# Level_Shifter.net
KiCad netlist of a schematic drawn in Altium Designer
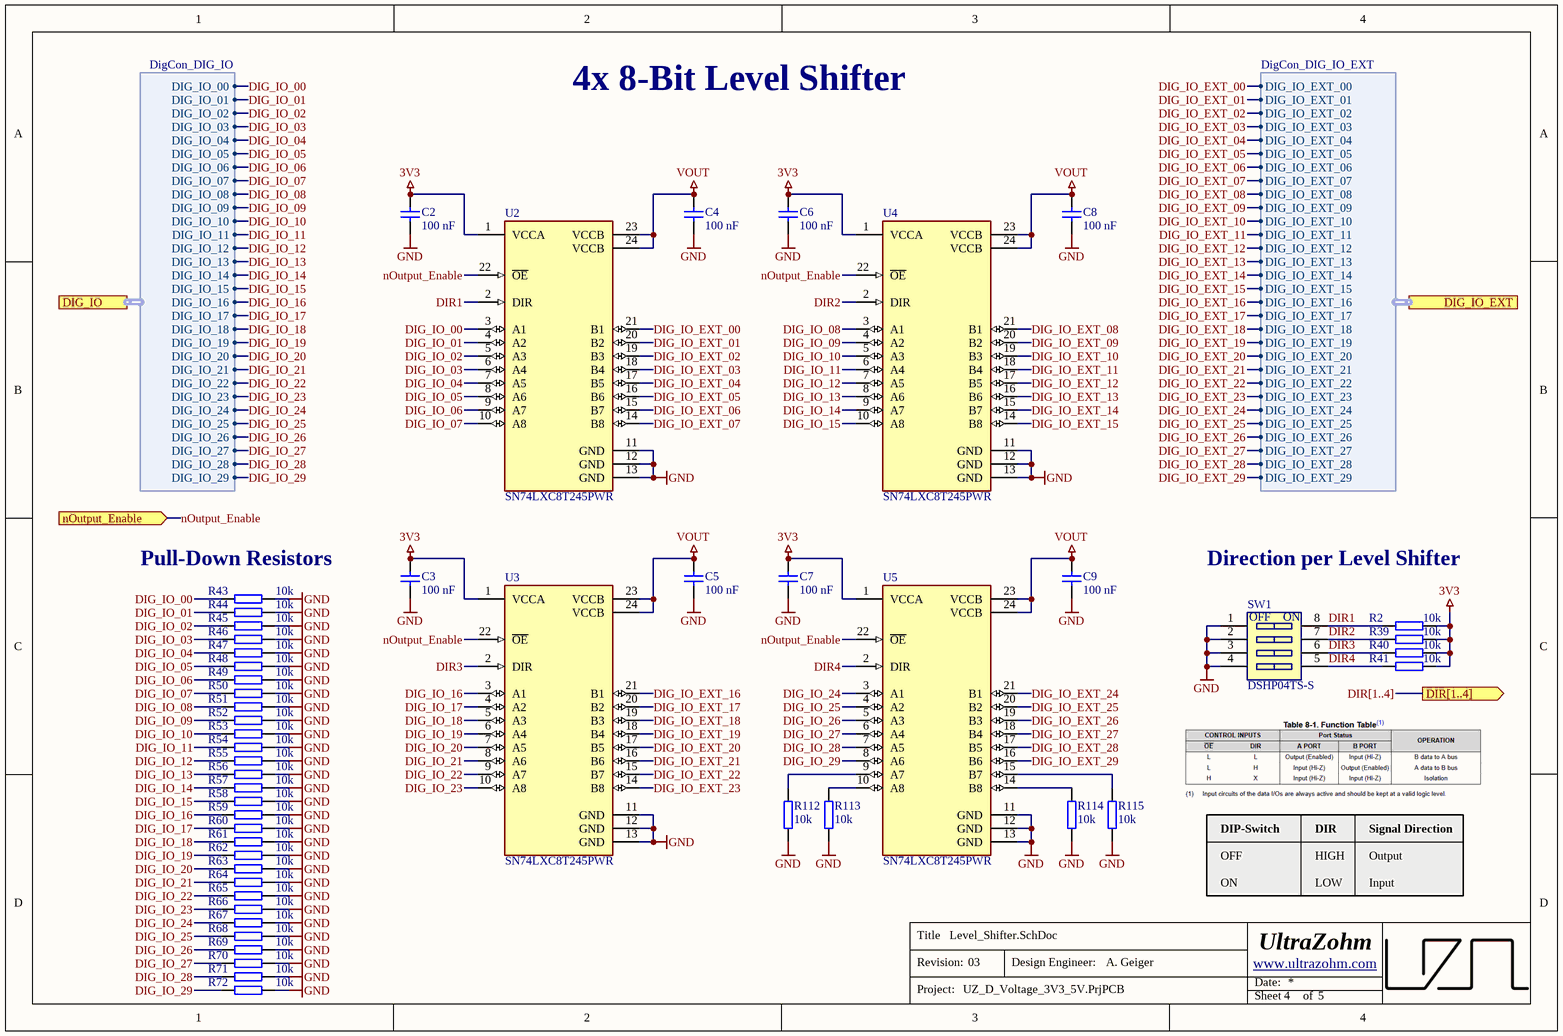
[diagram p0: Level_Shifter.SchDoc]

(export (version "E")
  (design (tool "Eeschema 10.0.6"))
  (components
    (comp (ref "C2")
      (value "100 nF")
      (footprint "C_0603_TE")
      (description "Generic capacitor")
      (fields
        (field (name "MANUFACTURER PART NUMBER") "UZgen_C_0603_100nF_50V_X7R")
        (field (name "MANUFACTURER") "UZgen")
        (field (name "CREATED FROM") "AGeiger")
      )
      (libsource (lib "user") (part "CAP-NP"))
    )
    (comp (ref "C3")
      (value "100 nF")
      (footprint "C_0603_TE")
      (description "Generic capacitor")
      (fields
        (field (name "MANUFACTURER PART NUMBER") "UZgen_C_0603_100nF_50V_X7R")
        (field (name "MANUFACTURER") "UZgen")
        (field (name "CREATED FROM") "AGeiger")
      )
      (libsource (lib "user") (part "CAP-NP"))
    )
    (comp (ref "C4")
      (value "100 nF")
      (footprint "C_0603_TE")
      (description "Generic capacitor")
      (fields
        (field (name "MANUFACTURER PART NUMBER") "UZgen_C_0603_100nF_50V_X7R")
        (field (name "MANUFACTURER") "UZgen")
        (field (name "CREATED FROM") "AGeiger")
      )
      (libsource (lib "user") (part "CAP-NP"))
    )
    (comp (ref "C5")
      (value "100 nF")
      (footprint "C_0603_TE")
      (description "Generic capacitor")
      (fields
        (field (name "MANUFACTURER PART NUMBER") "UZgen_C_0603_100nF_50V_X7R")
        (field (name "MANUFACTURER") "UZgen")
        (field (name "CREATED FROM") "AGeiger")
      )
      (libsource (lib "user") (part "CAP-NP"))
    )
    (comp (ref "C6")
      (value "100 nF")
      (footprint "C_0603_TE")
      (description "Generic capacitor")
      (fields
        (field (name "MANUFACTURER PART NUMBER") "UZgen_C_0603_100nF_50V_X7R")
        (field (name "MANUFACTURER") "UZgen")
        (field (name "CREATED FROM") "AGeiger")
      )
      (libsource (lib "user") (part "CAP-NP"))
    )
    (comp (ref "C7")
      (value "100 nF")
      (footprint "C_0603_TE")
      (description "Generic capacitor")
      (fields
        (field (name "MANUFACTURER PART NUMBER") "UZgen_C_0603_100nF_50V_X7R")
        (field (name "MANUFACTURER") "UZgen")
        (field (name "CREATED FROM") "AGeiger")
      )
      (libsource (lib "user") (part "CAP-NP"))
    )
    (comp (ref "C8")
      (value "100 nF")
      (footprint "C_0603_TE")
      (description "Generic capacitor")
      (fields
        (field (name "MANUFACTURER PART NUMBER") "UZgen_C_0603_100nF_50V_X7R")
        (field (name "MANUFACTURER") "UZgen")
        (field (name "CREATED FROM") "AGeiger")
      )
      (libsource (lib "user") (part "CAP-NP"))
    )
    (comp (ref "C9")
      (value "100 nF")
      (footprint "C_0603_TE")
      (description "Generic capacitor")
      (fields
        (field (name "MANUFACTURER PART NUMBER") "UZgen_C_0603_100nF_50V_X7R")
        (field (name "MANUFACTURER") "UZgen")
        (field (name "CREATED FROM") "AGeiger")
      )
      (libsource (lib "user") (part "CAP-NP"))
    )
    (comp (ref "R2")
      (value "10k")
      (footprint "R_0603_TE")
      (description "Generic resistor")
      (fields
        (field (name "MANUFACTURER PART NUMBER") "UZgen_R_0603_10k")
        (field (name "MANUFACTURER") "UZgen")
        (field (name "CREATED FROM") "AGeiger")
      )
      (libsource (lib "user") (part "RES"))
    )
    (comp (ref "R39")
      (value "10k")
      (footprint "R_0603_TE")
      (description "Generic resistor")
      (fields
        (field (name "MANUFACTURER PART NUMBER") "UZgen_R_0603_10k")
        (field (name "MANUFACTURER") "UZgen")
        (field (name "CREATED FROM") "AGeiger")
      )
      (libsource (lib "user") (part "RES"))
    )
    (comp (ref "R40")
      (value "10k")
      (footprint "R_0603_TE")
      (description "Generic resistor")
      (fields
        (field (name "MANUFACTURER PART NUMBER") "UZgen_R_0603_10k")
        (field (name "MANUFACTURER") "UZgen")
        (field (name "CREATED FROM") "AGeiger")
      )
      (libsource (lib "user") (part "RES"))
    )
    (comp (ref "R41")
      (value "10k")
      (footprint "R_0603_TE")
      (description "Generic resistor")
      (fields
        (field (name "MANUFACTURER PART NUMBER") "UZgen_R_0603_10k")
        (field (name "MANUFACTURER") "UZgen")
        (field (name "CREATED FROM") "AGeiger")
      )
      (libsource (lib "user") (part "RES"))
    )
    (comp (ref "R43")
      (value "10k")
      (footprint "R_0603_TE")
      (description "Generic resistor")
      (fields
        (field (name "MANUFACTURER PART NUMBER") "UZgen_R_0603_10k")
        (field (name "MANUFACTURER") "UZgen")
        (field (name "CREATED FROM") "AGeiger")
      )
      (libsource (lib "user") (part "RES"))
    )
    (comp (ref "R44")
      (value "10k")
      (footprint "R_0603_TE")
      (description "Generic resistor")
      (fields
        (field (name "MANUFACTURER PART NUMBER") "UZgen_R_0603_10k")
        (field (name "MANUFACTURER") "UZgen")
        (field (name "CREATED FROM") "AGeiger")
      )
      (libsource (lib "user") (part "RES"))
    )
    (comp (ref "R45")
      (value "10k")
      (footprint "R_0603_TE")
      (description "Generic resistor")
      (fields
        (field (name "MANUFACTURER PART NUMBER") "UZgen_R_0603_10k")
        (field (name "MANUFACTURER") "UZgen")
        (field (name "CREATED FROM") "AGeiger")
      )
      (libsource (lib "user") (part "RES"))
    )
    (comp (ref "R46")
      (value "10k")
      (footprint "R_0603_TE")
      (description "Generic resistor")
      (fields
        (field (name "MANUFACTURER PART NUMBER") "UZgen_R_0603_10k")
        (field (name "MANUFACTURER") "UZgen")
        (field (name "CREATED FROM") "AGeiger")
      )
      (libsource (lib "user") (part "RES"))
    )
    (comp (ref "R47")
      (value "10k")
      (footprint "R_0603_TE")
      (description "Generic resistor")
      (fields
        (field (name "MANUFACTURER PART NUMBER") "UZgen_R_0603_10k")
        (field (name "MANUFACTURER") "UZgen")
        (field (name "CREATED FROM") "AGeiger")
      )
      (libsource (lib "user") (part "RES"))
    )
    (comp (ref "R48")
      (value "10k")
      (footprint "R_0603_TE")
      (description "Generic resistor")
      (fields
        (field (name "MANUFACTURER PART NUMBER") "UZgen_R_0603_10k")
        (field (name "MANUFACTURER") "UZgen")
        (field (name "CREATED FROM") "AGeiger")
      )
      (libsource (lib "user") (part "RES"))
    )
    (comp (ref "R49")
      (value "10k")
      (footprint "R_0603_TE")
      (description "Generic resistor")
      (fields
        (field (name "MANUFACTURER PART NUMBER") "UZgen_R_0603_10k")
        (field (name "MANUFACTURER") "UZgen")
        (field (name "CREATED FROM") "AGeiger")
      )
      (libsource (lib "user") (part "RES"))
    )
    (comp (ref "R50")
      (value "10k")
      (footprint "R_0603_TE")
      (description "Generic resistor")
      (fields
        (field (name "MANUFACTURER PART NUMBER") "UZgen_R_0603_10k")
        (field (name "MANUFACTURER") "UZgen")
        (field (name "CREATED FROM") "AGeiger")
      )
      (libsource (lib "user") (part "RES"))
    )
    (comp (ref "R51")
      (value "10k")
      (footprint "R_0603_TE")
      (description "Generic resistor")
      (fields
        (field (name "MANUFACTURER PART NUMBER") "UZgen_R_0603_10k")
        (field (name "MANUFACTURER") "UZgen")
        (field (name "CREATED FROM") "AGeiger")
      )
      (libsource (lib "user") (part "RES"))
    )
    (comp (ref "R52")
      (value "10k")
      (footprint "R_0603_TE")
      (description "Generic resistor")
      (fields
        (field (name "MANUFACTURER PART NUMBER") "UZgen_R_0603_10k")
        (field (name "MANUFACTURER") "UZgen")
        (field (name "CREATED FROM") "AGeiger")
      )
      (libsource (lib "user") (part "RES"))
    )
    (comp (ref "R53")
      (value "10k")
      (footprint "R_0603_TE")
      (description "Generic resistor")
      (fields
        (field (name "MANUFACTURER PART NUMBER") "UZgen_R_0603_10k")
        (field (name "MANUFACTURER") "UZgen")
        (field (name "CREATED FROM") "AGeiger")
      )
      (libsource (lib "user") (part "RES"))
    )
    (comp (ref "R54")
      (value "10k")
      (footprint "R_0603_TE")
      (description "Generic resistor")
      (fields
        (field (name "MANUFACTURER PART NUMBER") "UZgen_R_0603_10k")
        (field (name "MANUFACTURER") "UZgen")
        (field (name "CREATED FROM") "AGeiger")
      )
      (libsource (lib "user") (part "RES"))
    )
    (comp (ref "R55")
      (value "10k")
      (footprint "R_0603_TE")
      (description "Generic resistor")
      (fields
        (field (name "MANUFACTURER PART NUMBER") "UZgen_R_0603_10k")
        (field (name "MANUFACTURER") "UZgen")
        (field (name "CREATED FROM") "AGeiger")
      )
      (libsource (lib "user") (part "RES"))
    )
    (comp (ref "R56")
      (value "10k")
      (footprint "R_0603_TE")
      (description "Generic resistor")
      (fields
        (field (name "MANUFACTURER PART NUMBER") "UZgen_R_0603_10k")
        (field (name "MANUFACTURER") "UZgen")
        (field (name "CREATED FROM") "AGeiger")
      )
      (libsource (lib "user") (part "RES"))
    )
    (comp (ref "R57")
      (value "10k")
      (footprint "R_0603_TE")
      (description "Generic resistor")
      (fields
        (field (name "MANUFACTURER PART NUMBER") "UZgen_R_0603_10k")
        (field (name "MANUFACTURER") "UZgen")
        (field (name "CREATED FROM") "AGeiger")
      )
      (libsource (lib "user") (part "RES"))
    )
    (comp (ref "R58")
      (value "10k")
      (footprint "R_0603_TE")
      (description "Generic resistor")
      (fields
        (field (name "MANUFACTURER PART NUMBER") "UZgen_R_0603_10k")
        (field (name "MANUFACTURER") "UZgen")
        (field (name "CREATED FROM") "AGeiger")
      )
      (libsource (lib "user") (part "RES"))
    )
    (comp (ref "R59")
      (value "10k")
      (footprint "R_0603_TE")
      (description "Generic resistor")
      (fields
        (field (name "MANUFACTURER PART NUMBER") "UZgen_R_0603_10k")
        (field (name "MANUFACTURER") "UZgen")
        (field (name "CREATED FROM") "AGeiger")
      )
      (libsource (lib "user") (part "RES"))
    )
    (comp (ref "R60")
      (value "10k")
      (footprint "R_0603_TE")
      (description "Generic resistor")
      (fields
        (field (name "MANUFACTURER PART NUMBER") "UZgen_R_0603_10k")
        (field (name "MANUFACTURER") "UZgen")
        (field (name "CREATED FROM") "AGeiger")
      )
      (libsource (lib "user") (part "RES"))
    )
    (comp (ref "R61")
      (value "10k")
      (footprint "R_0603_TE")
      (description "Generic resistor")
      (fields
        (field (name "MANUFACTURER PART NUMBER") "UZgen_R_0603_10k")
        (field (name "MANUFACTURER") "UZgen")
        (field (name "CREATED FROM") "AGeiger")
      )
      (libsource (lib "user") (part "RES"))
    )
    (comp (ref "R62")
      (value "10k")
      (footprint "R_0603_TE")
      (description "Generic resistor")
      (fields
        (field (name "MANUFACTURER PART NUMBER") "UZgen_R_0603_10k")
        (field (name "MANUFACTURER") "UZgen")
        (field (name "CREATED FROM") "AGeiger")
      )
      (libsource (lib "user") (part "RES"))
    )
    (comp (ref "R63")
      (value "10k")
      (footprint "R_0603_TE")
      (description "Generic resistor")
      (fields
        (field (name "MANUFACTURER PART NUMBER") "UZgen_R_0603_10k")
        (field (name "MANUFACTURER") "UZgen")
        (field (name "CREATED FROM") "AGeiger")
      )
      (libsource (lib "user") (part "RES"))
    )
    (comp (ref "R64")
      (value "10k")
      (footprint "R_0603_TE")
      (description "Generic resistor")
      (fields
        (field (name "MANUFACTURER PART NUMBER") "UZgen_R_0603_10k")
        (field (name "MANUFACTURER") "UZgen")
        (field (name "CREATED FROM") "AGeiger")
      )
      (libsource (lib "user") (part "RES"))
    )
    (comp (ref "R65")
      (value "10k")
      (footprint "R_0603_TE")
      (description "Generic resistor")
      (fields
        (field (name "MANUFACTURER PART NUMBER") "UZgen_R_0603_10k")
        (field (name "MANUFACTURER") "UZgen")
        (field (name "CREATED FROM") "AGeiger")
      )
      (libsource (lib "user") (part "RES"))
    )
    (comp (ref "R66")
      (value "10k")
      (footprint "R_0603_TE")
      (description "Generic resistor")
      (fields
        (field (name "MANUFACTURER PART NUMBER") "UZgen_R_0603_10k")
        (field (name "MANUFACTURER") "UZgen")
        (field (name "CREATED FROM") "AGeiger")
      )
      (libsource (lib "user") (part "RES"))
    )
    (comp (ref "R67")
      (value "10k")
      (footprint "R_0603_TE")
      (description "Generic resistor")
      (fields
        (field (name "MANUFACTURER PART NUMBER") "UZgen_R_0603_10k")
        (field (name "MANUFACTURER") "UZgen")
        (field (name "CREATED FROM") "AGeiger")
      )
      (libsource (lib "user") (part "RES"))
    )
    (comp (ref "R68")
      (value "10k")
      (footprint "R_0603_TE")
      (description "Generic resistor")
      (fields
        (field (name "MANUFACTURER PART NUMBER") "UZgen_R_0603_10k")
        (field (name "MANUFACTURER") "UZgen")
        (field (name "CREATED FROM") "AGeiger")
      )
      (libsource (lib "user") (part "RES"))
    )
    (comp (ref "R69")
      (value "10k")
      (footprint "R_0603_TE")
      (description "Generic resistor")
      (fields
        (field (name "MANUFACTURER PART NUMBER") "UZgen_R_0603_10k")
        (field (name "MANUFACTURER") "UZgen")
        (field (name "CREATED FROM") "AGeiger")
      )
      (libsource (lib "user") (part "RES"))
    )
    (comp (ref "R70")
      (value "10k")
      (footprint "R_0603_TE")
      (description "Generic resistor")
      (fields
        (field (name "MANUFACTURER PART NUMBER") "UZgen_R_0603_10k")
        (field (name "MANUFACTURER") "UZgen")
        (field (name "CREATED FROM") "AGeiger")
      )
      (libsource (lib "user") (part "RES"))
    )
    (comp (ref "R71")
      (value "10k")
      (footprint "R_0603_TE")
      (description "Generic resistor")
      (fields
        (field (name "MANUFACTURER PART NUMBER") "UZgen_R_0603_10k")
        (field (name "MANUFACTURER") "UZgen")
        (field (name "CREATED FROM") "AGeiger")
      )
      (libsource (lib "user") (part "RES"))
    )
    (comp (ref "R72")
      (value "10k")
      (footprint "R_0603_TE")
      (description "Generic resistor")
      (fields
        (field (name "MANUFACTURER PART NUMBER") "UZgen_R_0603_10k")
        (field (name "MANUFACTURER") "UZgen")
        (field (name "CREATED FROM") "AGeiger")
      )
      (libsource (lib "user") (part "RES"))
    )
    (comp (ref "R112")
      (value "10k")
      (footprint "R_0603_TE")
      (description "Generic resistor")
      (fields
        (field (name "MANUFACTURER PART NUMBER") "UZgen_R_0603_10k")
        (field (name "MANUFACTURER") "UZgen")
        (field (name "CREATED FROM") "AGeiger")
      )
      (libsource (lib "user") (part "RES"))
    )
    (comp (ref "R113")
      (value "10k")
      (footprint "R_0603_TE")
      (description "Generic resistor")
      (fields
        (field (name "MANUFACTURER PART NUMBER") "UZgen_R_0603_10k")
        (field (name "MANUFACTURER") "UZgen")
        (field (name "CREATED FROM") "AGeiger")
      )
      (libsource (lib "user") (part "RES"))
    )
    (comp (ref "R114")
      (value "10k")
      (footprint "R_0603_TE")
      (description "Generic resistor")
      (fields
        (field (name "MANUFACTURER PART NUMBER") "UZgen_R_0603_10k")
        (field (name "MANUFACTURER") "UZgen")
        (field (name "CREATED FROM") "AGeiger")
      )
      (libsource (lib "user") (part "RES"))
    )
    (comp (ref "R115")
      (value "10k")
      (footprint "R_0603_TE")
      (description "Generic resistor")
      (fields
        (field (name "MANUFACTURER PART NUMBER") "UZgen_R_0603_10k")
        (field (name "MANUFACTURER") "UZgen")
        (field (name "CREATED FROM") "AGeiger")
      )
      (libsource (lib "user") (part "RES"))
    )
    (comp (ref "SW1")
      (value "DSHP04TS-S")
      (footprint "416131160804")
      (description "04p, 1.27mm Pitch, Horizontal, HP Type, SMT, flat Actuator, black, with Tape, T&R")
      (fields
        (field (name "MANUFACTURER") "XKB Connectivity")
        (field (name "LCSC PART NUMBER") "C319050")
        (field (name "CREATED FROM") "T. Wendt")
      )
      (libsource (lib "user") (part "DIP-SW-4p"))
    )
    (comp (ref "U2")
      (value "SN74LXC8T245PWR")
      (footprint "TSSOP-24")
      (description "8-bit Dual-Supply Bus Transceiver with Configurable Level Shifting and 3-State Outputs")
      (fields
        (field (name "MANUFACTURER") "Texas Instruments")
        (field (name "LCSC PART NUMBER") "C4363995")
        (field (name "CREATED FROM") "AGeiger")
      )
      (libsource (lib "user") (part "SN74LXC8T245"))
    )
    (comp (ref "U3")
      (value "SN74LXC8T245PWR")
      (footprint "TSSOP-24")
      (description "8-bit Dual-Supply Bus Transceiver with Configurable Level Shifting and 3-State Outputs")
      (fields
        (field (name "MANUFACTURER") "Texas Instruments")
        (field (name "LCSC PART NUMBER") "C4363995")
        (field (name "CREATED FROM") "AGeiger")
      )
      (libsource (lib "user") (part "SN74LXC8T245"))
    )
    (comp (ref "U4")
      (value "SN74LXC8T245PWR")
      (footprint "TSSOP-24")
      (description "8-bit Dual-Supply Bus Transceiver with Configurable Level Shifting and 3-State Outputs")
      (fields
        (field (name "MANUFACTURER") "Texas Instruments")
        (field (name "LCSC PART NUMBER") "C4363995")
        (field (name "CREATED FROM") "AGeiger")
      )
      (libsource (lib "user") (part "SN74LXC8T245"))
    )
    (comp (ref "U5")
      (value "SN74LXC8T245PWR")
      (footprint "TSSOP-24")
      (description "8-bit Dual-Supply Bus Transceiver with Configurable Level Shifting and 3-State Outputs")
      (fields
        (field (name "MANUFACTURER") "Texas Instruments")
        (field (name "LCSC PART NUMBER") "C4363995")
        (field (name "CREATED FROM") "AGeiger")
      )
      (libsource (lib "user") (part "SN74LXC8T245"))
    )
  )
  (nets
    (net (code "3") (name "/DIG_IO_00") (class "Default")
      (node (ref "R43") (pin "1") (pinfunction "1_1") (pintype "passive"))
      (node (ref "U2") (pin "3") (pinfunction "A1_3") (pintype "bidirectional"))
    )
    (net (code "4") (name "/DIG_IO_01") (class "Default")
      (node (ref "R44") (pin "1") (pinfunction "1_1") (pintype "passive"))
      (node (ref "U2") (pin "4") (pinfunction "A2_4") (pintype "bidirectional"))
    )
    (net (code "5") (name "/DIG_IO_02") (class "Default")
      (node (ref "R45") (pin "1") (pinfunction "1_1") (pintype "passive"))
      (node (ref "U2") (pin "5") (pinfunction "A3_5") (pintype "bidirectional"))
    )
    (net (code "6") (name "/DIG_IO_03") (class "Default")
      (node (ref "R46") (pin "1") (pinfunction "1_1") (pintype "passive"))
      (node (ref "U2") (pin "6") (pinfunction "A4_6") (pintype "bidirectional"))
    )
    (net (code "7") (name "/DIG_IO_04") (class "Default")
      (node (ref "R47") (pin "1") (pinfunction "1_1") (pintype "passive"))
      (node (ref "U2") (pin "7") (pinfunction "A5_7") (pintype "bidirectional"))
    )
    (net (code "8") (name "/DIG_IO_05") (class "Default")
      (node (ref "R48") (pin "1") (pinfunction "1_1") (pintype "passive"))
      (node (ref "U2") (pin "8") (pinfunction "A6_8") (pintype "bidirectional"))
    )
    (net (code "9") (name "/DIG_IO_06") (class "Default")
      (node (ref "R49") (pin "1") (pinfunction "1_1") (pintype "passive"))
      (node (ref "U2") (pin "9") (pinfunction "A7_9") (pintype "bidirectional"))
    )
    (net (code "10") (name "/DIG_IO_07") (class "Default")
      (node (ref "R50") (pin "1") (pinfunction "1_1") (pintype "passive"))
      (node (ref "U2") (pin "10") (pinfunction "A8_10") (pintype "bidirectional"))
    )
    (net (code "11") (name "/DIG_IO_08") (class "Default")
      (node (ref "R51") (pin "1") (pinfunction "1_1") (pintype "passive"))
      (node (ref "U4") (pin "3") (pinfunction "A1_3") (pintype "bidirectional"))
    )
    (net (code "12") (name "/DIG_IO_09") (class "Default")
      (node (ref "R52") (pin "1") (pinfunction "1_1") (pintype "passive"))
      (node (ref "U4") (pin "4") (pinfunction "A2_4") (pintype "bidirectional"))
    )
    (net (code "13") (name "/DIG_IO_10") (class "Default")
      (node (ref "R53") (pin "1") (pinfunction "1_1") (pintype "passive"))
      (node (ref "U4") (pin "5") (pinfunction "A3_5") (pintype "bidirectional"))
    )
    (net (code "14") (name "/DIG_IO_11") (class "Default")
      (node (ref "R54") (pin "1") (pinfunction "1_1") (pintype "passive"))
      (node (ref "U4") (pin "6") (pinfunction "A4_6") (pintype "bidirectional"))
    )
    (net (code "15") (name "/DIG_IO_12") (class "Default")
      (node (ref "R55") (pin "1") (pinfunction "1_1") (pintype "passive"))
      (node (ref "U4") (pin "7") (pinfunction "A5_7") (pintype "bidirectional"))
    )
    (net (code "16") (name "/DIG_IO_13") (class "Default")
      (node (ref "R56") (pin "1") (pinfunction "1_1") (pintype "passive"))
      (node (ref "U4") (pin "8") (pinfunction "A6_8") (pintype "bidirectional"))
    )
    (net (code "17") (name "/DIG_IO_14") (class "Default")
      (node (ref "R57") (pin "1") (pinfunction "1_1") (pintype "passive"))
      (node (ref "U4") (pin "9") (pinfunction "A7_9") (pintype "bidirectional"))
    )
    (net (code "18") (name "/DIG_IO_15") (class "Default")
      (node (ref "R58") (pin "1") (pinfunction "1_1") (pintype "passive"))
      (node (ref "U4") (pin "10") (pinfunction "A8_10") (pintype "bidirectional"))
    )
    (net (code "19") (name "/DIG_IO_16") (class "Default")
      (node (ref "R59") (pin "1") (pinfunction "1_1") (pintype "passive"))
      (node (ref "U3") (pin "3") (pinfunction "A1_3") (pintype "bidirectional"))
    )
    (net (code "20") (name "/DIG_IO_17") (class "Default")
      (node (ref "R60") (pin "1") (pinfunction "1_1") (pintype "passive"))
      (node (ref "U3") (pin "4") (pinfunction "A2_4") (pintype "bidirectional"))
    )
    (net (code "21") (name "/DIG_IO_18") (class "Default")
      (node (ref "R61") (pin "1") (pinfunction "1_1") (pintype "passive"))
      (node (ref "U3") (pin "5") (pinfunction "A3_5") (pintype "bidirectional"))
    )
    (net (code "22") (name "/DIG_IO_19") (class "Default")
      (node (ref "R62") (pin "1") (pinfunction "1_1") (pintype "passive"))
      (node (ref "U3") (pin "6") (pinfunction "A4_6") (pintype "bidirectional"))
    )
    (net (code "23") (name "/DIG_IO_20") (class "Default")
      (node (ref "R63") (pin "1") (pinfunction "1_1") (pintype "passive"))
      (node (ref "U3") (pin "7") (pinfunction "A5_7") (pintype "bidirectional"))
    )
    (net (code "24") (name "/DIG_IO_21") (class "Default")
      (node (ref "R64") (pin "1") (pinfunction "1_1") (pintype "passive"))
      (node (ref "U3") (pin "8") (pinfunction "A6_8") (pintype "bidirectional"))
    )
    (net (code "25") (name "/DIG_IO_22") (class "Default")
      (node (ref "R65") (pin "1") (pinfunction "1_1") (pintype "passive"))
      (node (ref "U3") (pin "9") (pinfunction "A7_9") (pintype "bidirectional"))
    )
    (net (code "26") (name "/DIG_IO_23") (class "Default")
      (node (ref "R66") (pin "1") (pinfunction "1_1") (pintype "passive"))
      (node (ref "U3") (pin "10") (pinfunction "A8_10") (pintype "bidirectional"))
    )
    (net (code "27") (name "/DIG_IO_24") (class "Default")
      (node (ref "R67") (pin "1") (pinfunction "1_1") (pintype "passive"))
      (node (ref "U5") (pin "3") (pinfunction "A1_3") (pintype "bidirectional"))
    )
    (net (code "28") (name "/DIG_IO_25") (class "Default")
      (node (ref "R68") (pin "1") (pinfunction "1_1") (pintype "passive"))
      (node (ref "U5") (pin "4") (pinfunction "A2_4") (pintype "bidirectional"))
    )
    (net (code "29") (name "/DIG_IO_26") (class "Default")
      (node (ref "R69") (pin "1") (pinfunction "1_1") (pintype "passive"))
      (node (ref "U5") (pin "5") (pinfunction "A3_5") (pintype "bidirectional"))
    )
    (net (code "30") (name "/DIG_IO_27") (class "Default")
      (node (ref "R70") (pin "1") (pinfunction "1_1") (pintype "passive"))
      (node (ref "U5") (pin "6") (pinfunction "A4_6") (pintype "bidirectional"))
    )
    (net (code "31") (name "/DIG_IO_28") (class "Default")
      (node (ref "R71") (pin "1") (pinfunction "1_1") (pintype "passive"))
      (node (ref "U5") (pin "7") (pinfunction "A5_7") (pintype "bidirectional"))
    )
    (net (code "32") (name "/DIG_IO_29") (class "Default")
      (node (ref "R72") (pin "1") (pinfunction "1_1") (pintype "passive"))
      (node (ref "U5") (pin "8") (pinfunction "A6_8") (pintype "bidirectional"))
    )
    (net (code "33") (name "/DIG_IO_EXT_00") (class "Default")
      (node (ref "U2") (pin "21") (pinfunction "B1_21") (pintype "bidirectional"))
    )
    (net (code "34") (name "/DIG_IO_EXT_01") (class "Default")
      (node (ref "U2") (pin "20") (pinfunction "B2_20") (pintype "bidirectional"))
    )
    (net (code "35") (name "/DIG_IO_EXT_02") (class "Default")
      (node (ref "U2") (pin "19") (pinfunction "B3_19") (pintype "bidirectional"))
    )
    (net (code "36") (name "/DIG_IO_EXT_03") (class "Default")
      (node (ref "U2") (pin "18") (pinfunction "B4_18") (pintype "bidirectional"))
    )
    (net (code "37") (name "/DIG_IO_EXT_04") (class "Default")
      (node (ref "U2") (pin "17") (pinfunction "B5_17") (pintype "bidirectional"))
    )
    (net (code "38") (name "/DIG_IO_EXT_05") (class "Default")
      (node (ref "U2") (pin "16") (pinfunction "B6_16") (pintype "bidirectional"))
    )
    (net (code "39") (name "/DIG_IO_EXT_06") (class "Default")
      (node (ref "U2") (pin "15") (pinfunction "B7_15") (pintype "bidirectional"))
    )
    (net (code "40") (name "/DIG_IO_EXT_07") (class "Default")
      (node (ref "U2") (pin "14") (pinfunction "B8_14") (pintype "bidirectional"))
    )
    (net (code "41") (name "/DIG_IO_EXT_08") (class "Default")
      (node (ref "U4") (pin "21") (pinfunction "B1_21") (pintype "bidirectional"))
    )
    (net (code "42") (name "/DIG_IO_EXT_09") (class "Default")
      (node (ref "U4") (pin "20") (pinfunction "B2_20") (pintype "bidirectional"))
    )
    (net (code "43") (name "/DIG_IO_EXT_10") (class "Default")
      (node (ref "U4") (pin "19") (pinfunction "B3_19") (pintype "bidirectional"))
    )
    (net (code "44") (name "/DIG_IO_EXT_11") (class "Default")
      (node (ref "U4") (pin "18") (pinfunction "B4_18") (pintype "bidirectional"))
    )
    (net (code "45") (name "/DIG_IO_EXT_12") (class "Default")
      (node (ref "U4") (pin "17") (pinfunction "B5_17") (pintype "bidirectional"))
    )
    (net (code "46") (name "/DIG_IO_EXT_13") (class "Default")
      (node (ref "U4") (pin "16") (pinfunction "B6_16") (pintype "bidirectional"))
    )
    (net (code "47") (name "/DIG_IO_EXT_14") (class "Default")
      (node (ref "U4") (pin "15") (pinfunction "B7_15") (pintype "bidirectional"))
    )
    (net (code "48") (name "/DIG_IO_EXT_15") (class "Default")
      (node (ref "U4") (pin "14") (pinfunction "B8_14") (pintype "bidirectional"))
    )
    (net (code "49") (name "/DIG_IO_EXT_16") (class "Default")
      (node (ref "U3") (pin "21") (pinfunction "B1_21") (pintype "bidirectional"))
    )
    (net (code "50") (name "/DIG_IO_EXT_17") (class "Default")
      (node (ref "U3") (pin "20") (pinfunction "B2_20") (pintype "bidirectional"))
    )
    (net (code "51") (name "/DIG_IO_EXT_18") (class "Default")
      (node (ref "U3") (pin "19") (pinfunction "B3_19") (pintype "bidirectional"))
    )
    (net (code "52") (name "/DIG_IO_EXT_19") (class "Default")
      (node (ref "U3") (pin "18") (pinfunction "B4_18") (pintype "bidirectional"))
    )
    (net (code "53") (name "/DIG_IO_EXT_20") (class "Default")
      (node (ref "U3") (pin "17") (pinfunction "B5_17") (pintype "bidirectional"))
    )
    (net (code "54") (name "/DIG_IO_EXT_21") (class "Default")
      (node (ref "U3") (pin "16") (pinfunction "B6_16") (pintype "bidirectional"))
    )
    (net (code "55") (name "/DIG_IO_EXT_22") (class "Default")
      (node (ref "U3") (pin "15") (pinfunction "B7_15") (pintype "bidirectional"))
    )
    (net (code "56") (name "/DIG_IO_EXT_23") (class "Default")
      (node (ref "U3") (pin "14") (pinfunction "B8_14") (pintype "bidirectional"))
    )
    (net (code "57") (name "/DIG_IO_EXT_24") (class "Default")
      (node (ref "U5") (pin "21") (pinfunction "B1_21") (pintype "bidirectional"))
    )
    (net (code "58") (name "/DIG_IO_EXT_25") (class "Default")
      (node (ref "U5") (pin "20") (pinfunction "B2_20") (pintype "bidirectional"))
    )
    (net (code "59") (name "/DIG_IO_EXT_26") (class "Default")
      (node (ref "U5") (pin "19") (pinfunction "B3_19") (pintype "bidirectional"))
    )
    (net (code "60") (name "/DIG_IO_EXT_27") (class "Default")
      (node (ref "U5") (pin "18") (pinfunction "B4_18") (pintype "bidirectional"))
    )
    (net (code "61") (name "/DIG_IO_EXT_28") (class "Default")
      (node (ref "U5") (pin "17") (pinfunction "B5_17") (pintype "bidirectional"))
    )
    (net (code "62") (name "/DIG_IO_EXT_29") (class "Default")
      (node (ref "U5") (pin "16") (pinfunction "B6_16") (pintype "bidirectional"))
    )
    (net (code "63") (name "/DIR1") (class "Default")
      (node (ref "R2") (pin "1") (pinfunction "1_1") (pintype "passive"))
      (node (ref "SW1") (pin "8") (pinfunction "8_8") (pintype "passive"))
      (node (ref "U2") (pin "2") (pinfunction "DIR_2") (pintype "input"))
    )
    (net (code "64") (name "/DIR2") (class "Default")
      (node (ref "R39") (pin "1") (pinfunction "1_1") (pintype "passive"))
      (node (ref "SW1") (pin "7") (pinfunction "7_7") (pintype "passive"))
      (node (ref "U4") (pin "2") (pinfunction "DIR_2") (pintype "input"))
    )
    (net (code "65") (name "/DIR3") (class "Default")
      (node (ref "R40") (pin "1") (pinfunction "1_1") (pintype "passive"))
      (node (ref "SW1") (pin "6") (pinfunction "6_6") (pintype "passive"))
      (node (ref "U3") (pin "2") (pinfunction "DIR_2") (pintype "input"))
    )
    (net (code "66") (name "/DIR4") (class "Default")
      (node (ref "R41") (pin "1") (pinfunction "1_1") (pintype "passive"))
      (node (ref "SW1") (pin "5") (pinfunction "5_5") (pintype "passive"))
      (node (ref "U5") (pin "2") (pinfunction "DIR_2") (pintype "input"))
    )
    (net (code "68") (name "/nOutput_Enable") (class "Default")
      (node (ref "U2") (pin "22") (pinfunction "~{OE}_22") (pintype "input"))
      (node (ref "U3") (pin "22") (pinfunction "~{OE}_22") (pintype "input"))
      (node (ref "U4") (pin "22") (pinfunction "~{OE}_22") (pintype "input"))
      (node (ref "U5") (pin "22") (pinfunction "~{OE}_22") (pintype "input"))
    )
    (net (code "71") (name "3V3") (class "Default")
      (node (ref "C2") (pin "1") (pinfunction "1_1") (pintype "passive"))
      (node (ref "C3") (pin "1") (pinfunction "1_1") (pintype "passive"))
      (node (ref "C6") (pin "1") (pinfunction "1_1") (pintype "passive"))
      (node (ref "C7") (pin "1") (pinfunction "1_1") (pintype "passive"))
      (node (ref "R2") (pin "2") (pinfunction "2_2") (pintype "passive"))
      (node (ref "R39") (pin "2") (pinfunction "2_2") (pintype "passive"))
      (node (ref "R40") (pin "2") (pinfunction "2_2") (pintype "passive"))
      (node (ref "R41") (pin "2") (pinfunction "2_2") (pintype "passive"))
      (node (ref "U2") (pin "1") (pinfunction "VCCA_1") (pintype "power_in"))
      (node (ref "U3") (pin "1") (pinfunction "VCCA_1") (pintype "power_in"))
      (node (ref "U4") (pin "1") (pinfunction "VCCA_1") (pintype "power_in"))
      (node (ref "U5") (pin "1") (pinfunction "VCCA_1") (pintype "power_in"))
    )
    (net (code "72") (name "GND") (class "Default")
      (node (ref "C2") (pin "2") (pinfunction "2_2") (pintype "passive"))
      (node (ref "C3") (pin "2") (pinfunction "2_2") (pintype "passive"))
      (node (ref "C4") (pin "2") (pinfunction "2_2") (pintype "passive"))
      (node (ref "C5") (pin "2") (pinfunction "2_2") (pintype "passive"))
      (node (ref "C6") (pin "2") (pinfunction "2_2") (pintype "passive"))
      (node (ref "C7") (pin "2") (pinfunction "2_2") (pintype "passive"))
      (node (ref "C8") (pin "2") (pinfunction "2_2") (pintype "passive"))
      (node (ref "C9") (pin "2") (pinfunction "2_2") (pintype "passive"))
      (node (ref "R112") (pin "1") (pinfunction "1_1") (pintype "passive"))
      (node (ref "R113") (pin "1") (pinfunction "1_1") (pintype "passive"))
      (node (ref "R114") (pin "1") (pinfunction "1_1") (pintype "passive"))
      (node (ref "R115") (pin "1") (pinfunction "1_1") (pintype "passive"))
      (node (ref "R43") (pin "2") (pinfunction "2_2") (pintype "passive"))
      (node (ref "R44") (pin "2") (pinfunction "2_2") (pintype "passive"))
      (node (ref "R45") (pin "2") (pinfunction "2_2") (pintype "passive"))
      (node (ref "R46") (pin "2") (pinfunction "2_2") (pintype "passive"))
      (node (ref "R47") (pin "2") (pinfunction "2_2") (pintype "passive"))
      (node (ref "R48") (pin "2") (pinfunction "2_2") (pintype "passive"))
      (node (ref "R49") (pin "2") (pinfunction "2_2") (pintype "passive"))
      (node (ref "R50") (pin "2") (pinfunction "2_2") (pintype "passive"))
      (node (ref "R51") (pin "2") (pinfunction "2_2") (pintype "passive"))
      (node (ref "R52") (pin "2") (pinfunction "2_2") (pintype "passive"))
      (node (ref "R53") (pin "2") (pinfunction "2_2") (pintype "passive"))
      (node (ref "R54") (pin "2") (pinfunction "2_2") (pintype "passive"))
      (node (ref "R55") (pin "2") (pinfunction "2_2") (pintype "passive"))
      (node (ref "R56") (pin "2") (pinfunction "2_2") (pintype "passive"))
      (node (ref "R57") (pin "2") (pinfunction "2_2") (pintype "passive"))
      (node (ref "R58") (pin "2") (pinfunction "2_2") (pintype "passive"))
      (node (ref "R59") (pin "2") (pinfunction "2_2") (pintype "passive"))
      (node (ref "R60") (pin "2") (pinfunction "2_2") (pintype "passive"))
      (node (ref "R61") (pin "2") (pinfunction "2_2") (pintype "passive"))
      (node (ref "R62") (pin "2") (pinfunction "2_2") (pintype "passive"))
      (node (ref "R63") (pin "2") (pinfunction "2_2") (pintype "passive"))
      (node (ref "R64") (pin "2") (pinfunction "2_2") (pintype "passive"))
      (node (ref "R65") (pin "2") (pinfunction "2_2") (pintype "passive"))
      (node (ref "R66") (pin "2") (pinfunction "2_2") (pintype "passive"))
      (node (ref "R67") (pin "2") (pinfunction "2_2") (pintype "passive"))
      (node (ref "R68") (pin "2") (pinfunction "2_2") (pintype "passive"))
      (node (ref "R69") (pin "2") (pinfunction "2_2") (pintype "passive"))
      (node (ref "R70") (pin "2") (pinfunction "2_2") (pintype "passive"))
      (node (ref "R71") (pin "2") (pinfunction "2_2") (pintype "passive"))
      (node (ref "R72") (pin "2") (pinfunction "2_2") (pintype "passive"))
      (node (ref "SW1") (pin "1") (pinfunction "1_1") (pintype "passive"))
      (node (ref "SW1") (pin "2") (pinfunction "2_2") (pintype "passive"))
      (node (ref "SW1") (pin "3") (pinfunction "3_3") (pintype "passive"))
      (node (ref "SW1") (pin "4") (pinfunction "4_4") (pintype "passive"))
      (node (ref "U2") (pin "11") (pinfunction "GND_11") (pintype "power_in"))
      (node (ref "U2") (pin "12") (pinfunction "GND_12") (pintype "power_in"))
      (node (ref "U2") (pin "13") (pinfunction "GND_13") (pintype "power_in"))
      (node (ref "U3") (pin "11") (pinfunction "GND_11") (pintype "power_in"))
      (node (ref "U3") (pin "12") (pinfunction "GND_12") (pintype "power_in"))
      (node (ref "U3") (pin "13") (pinfunction "GND_13") (pintype "power_in"))
      (node (ref "U4") (pin "11") (pinfunction "GND_11") (pintype "power_in"))
      (node (ref "U4") (pin "12") (pinfunction "GND_12") (pintype "power_in"))
      (node (ref "U4") (pin "13") (pinfunction "GND_13") (pintype "power_in"))
      (node (ref "U5") (pin "11") (pinfunction "GND_11") (pintype "power_in"))
      (node (ref "U5") (pin "12") (pinfunction "GND_12") (pintype "power_in"))
      (node (ref "U5") (pin "13") (pinfunction "GND_13") (pintype "power_in"))
    )
    (net (code "73") (name "Net-(U5-A7)") (class "Default")
      (node (ref "R112") (pin "2") (pinfunction "2_2") (pintype "passive"))
      (node (ref "U5") (pin "9") (pinfunction "A7_9") (pintype "bidirectional"))
    )
    (net (code "74") (name "Net-(U5-A8)") (class "Default")
      (node (ref "R113") (pin "2") (pinfunction "2_2") (pintype "passive"))
      (node (ref "U5") (pin "10") (pinfunction "A8_10") (pintype "bidirectional"))
    )
    (net (code "75") (name "Net-(U5-B7)") (class "Default")
      (node (ref "R115") (pin "2") (pinfunction "2_2") (pintype "passive"))
      (node (ref "U5") (pin "15") (pinfunction "B7_15") (pintype "bidirectional"))
    )
    (net (code "76") (name "Net-(U5-B8)") (class "Default")
      (node (ref "R114") (pin "2") (pinfunction "2_2") (pintype "passive"))
      (node (ref "U5") (pin "14") (pinfunction "B8_14") (pintype "bidirectional"))
    )
    (net (code "77") (name "VOUT") (class "Default")
      (node (ref "C4") (pin "1") (pinfunction "1_1") (pintype "passive"))
      (node (ref "C5") (pin "1") (pinfunction "1_1") (pintype "passive"))
      (node (ref "C8") (pin "1") (pinfunction "1_1") (pintype "passive"))
      (node (ref "C9") (pin "1") (pinfunction "1_1") (pintype "passive"))
      (node (ref "U2") (pin "23") (pinfunction "VCCB_23") (pintype "power_in"))
      (node (ref "U2") (pin "24") (pinfunction "VCCB_24") (pintype "power_in"))
      (node (ref "U3") (pin "23") (pinfunction "VCCB_23") (pintype "power_in"))
      (node (ref "U3") (pin "24") (pinfunction "VCCB_24") (pintype "power_in"))
      (node (ref "U4") (pin "23") (pinfunction "VCCB_23") (pintype "power_in"))
      (node (ref "U4") (pin "24") (pinfunction "VCCB_24") (pintype "power_in"))
      (node (ref "U5") (pin "23") (pinfunction "VCCB_23") (pintype "power_in"))
      (node (ref "U5") (pin "24") (pinfunction "VCCB_24") (pintype "power_in"))
    )
  )
)
